# Powerswitch_MUR3060.net
KiCad netlist of a schematic drawn in EAGLE
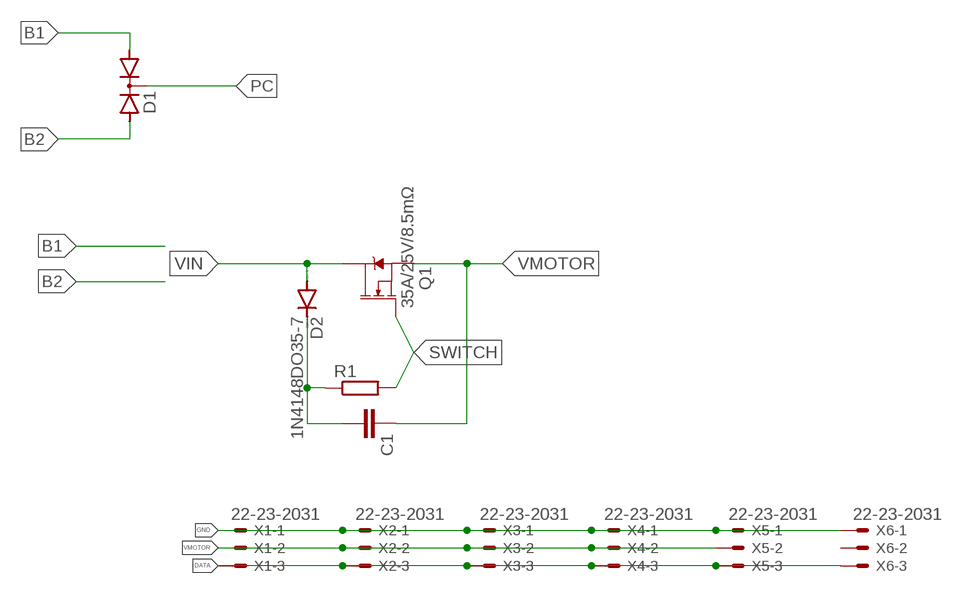
[diagram p0: schematic, sheet 1]

(export (version "E")
  (design (tool "Eeschema 10.0.6"))
  (components
    (comp (ref "C1")
      (value "C-EU025-030X050")
      (footprint "eagle-import:C025-030X050")
      (libsource (lib "eagle-import") (part "C-EU025-030X050"))
    )
    (comp (ref "D1")
      (value "DIODE-2AC|CATO220H")
      (footprint "eagle-import:TO220AB")
      (libsource (lib "eagle-import") (part "DIODE-2AC|CATO220H"))
    )
    (comp (ref "D2")
      (value "1N4148DO35-7")
      (footprint "eagle-import:DO35-7")
      (libsource (lib "eagle-import") (part "1N4148DO35-7"))
    )
    (comp (ref "Q1")
      (value "35A/25V/8.5mΩ")
      (footprint "eagle-import:DPAK")
      (libsource (lib "eagle-import") (part "MOSFET-NCH-FDD8780"))
    )
    (comp (ref "R1")
      (value "R-EU_0207/10")
      (footprint "eagle-import:0207_10")
      (libsource (lib "eagle-import") (part "R-EU_0207/10"))
    )
    (comp (ref "X1")
      (value "22-23-2031")
      (footprint "eagle-import:22-23-2031")
      (fields (field (name "MF") "MOLEX"))
      (libsource (lib "eagle-import") (part "22-23-2031"))
    )
    (comp (ref "X2")
      (value "22-23-2031")
      (footprint "eagle-import:22-23-2031")
      (fields (field (name "MF") "MOLEX"))
      (libsource (lib "eagle-import") (part "22-23-2031"))
    )
    (comp (ref "X3")
      (value "22-23-2031")
      (footprint "eagle-import:22-23-2031")
      (fields (field (name "MF") "MOLEX"))
      (libsource (lib "eagle-import") (part "22-23-2031"))
    )
    (comp (ref "X4")
      (value "22-23-2031")
      (footprint "eagle-import:22-23-2031")
      (fields (field (name "MF") "MOLEX"))
      (libsource (lib "eagle-import") (part "22-23-2031"))
    )
    (comp (ref "X5")
      (value "22-23-2031")
      (footprint "eagle-import:22-23-2031")
      (fields (field (name "MF") "MOLEX"))
      (libsource (lib "eagle-import") (part "22-23-2031"))
    )
    (comp (ref "X6")
      (value "22-23-2031")
      (footprint "eagle-import:22-23-2031")
      (fields (field (name "MF") "MOLEX"))
      (libsource (lib "eagle-import") (part "22-23-2031"))
    )
  )
  (nets
    (net (code "1") (name "B1") (class "Default")
      (node (ref "D1") (pin "A1") (pinfunction "A1_A1") (pintype "passive"))
    )
    (net (code "2") (name "B2") (class "Default")
      (node (ref "D1") (pin "A2") (pinfunction "A2_A2") (pintype "passive"))
    )
    (net (code "3") (name "DATA") (class "Default")
      (node (ref "X1") (pin "3") (pinfunction "S_3") (pintype "passive"))
      (node (ref "X2") (pin "3") (pinfunction "S_3") (pintype "passive"))
      (node (ref "X3") (pin "3") (pinfunction "S_3") (pintype "passive"))
      (node (ref "X4") (pin "3") (pinfunction "S_3") (pintype "passive"))
      (node (ref "X5") (pin "3") (pinfunction "S_3") (pintype "passive"))
      (node (ref "X6") (pin "3") (pinfunction "S_3") (pintype "passive"))
    )
    (net (code "4") (name "GND") (class "Default")
      (node (ref "X1") (pin "1") (pinfunction "S_1") (pintype "passive"))
      (node (ref "X2") (pin "1") (pinfunction "S_1") (pintype "passive"))
      (node (ref "X3") (pin "1") (pinfunction "S_1") (pintype "passive"))
      (node (ref "X4") (pin "1") (pinfunction "S_1") (pintype "passive"))
      (node (ref "X5") (pin "1") (pinfunction "S_1") (pintype "passive"))
      (node (ref "X6") (pin "1") (pinfunction "S_1") (pintype "passive"))
    )
    (net (code "5") (name "Net-(C1-Pad2)") (class "Default")
      (node (ref "C1") (pin "2") (pinfunction "2_2") (pintype "passive"))
      (node (ref "D2") (pin "C") (pinfunction "C_C") (pintype "passive"))
      (node (ref "R1") (pin "1") (pinfunction "1_1") (pintype "passive"))
    )
    (net (code "6") (name "PC") (class "Default")
      (node (ref "D1") (pin "C") (pinfunction "C_C") (pintype "passive"))
    )
    (net (code "7") (name "SWITCH") (class "Default")
      (node (ref "Q1") (pin "1") (pinfunction "G_1") (pintype "bidirectional"))
      (node (ref "R1") (pin "2") (pinfunction "2_2") (pintype "passive"))
    )
    (net (code "8") (name "VIN") (class "Default")
      (node (ref "D2") (pin "A") (pinfunction "A_A") (pintype "passive"))
      (node (ref "Q1") (pin "4") (pinfunction "D_4") (pintype "bidirectional"))
    )
    (net (code "9") (name "VMOTOR") (class "Default")
      (node (ref "C1") (pin "1") (pinfunction "1_1") (pintype "passive"))
      (node (ref "Q1") (pin "3") (pinfunction "S_3") (pintype "bidirectional"))
      (node (ref "X1") (pin "2") (pinfunction "S_2") (pintype "passive"))
      (node (ref "X2") (pin "2") (pinfunction "S_2") (pintype "passive"))
      (node (ref "X3") (pin "2") (pinfunction "S_2") (pintype "passive"))
      (node (ref "X4") (pin "2") (pinfunction "S_2") (pintype "passive"))
      (node (ref "X5") (pin "2") (pinfunction "S_2") (pintype "passive"))
    )
    (net (code "10") (name "unconnected-(X6B-S-Pad2)") (class "Default")
      (node (ref "X6") (pin "2") (pinfunction "S_2") (pintype "passive"))
    )
  )
)
